# TYPK.net
KiCad netlist of a schematic drawn in Altium Designer
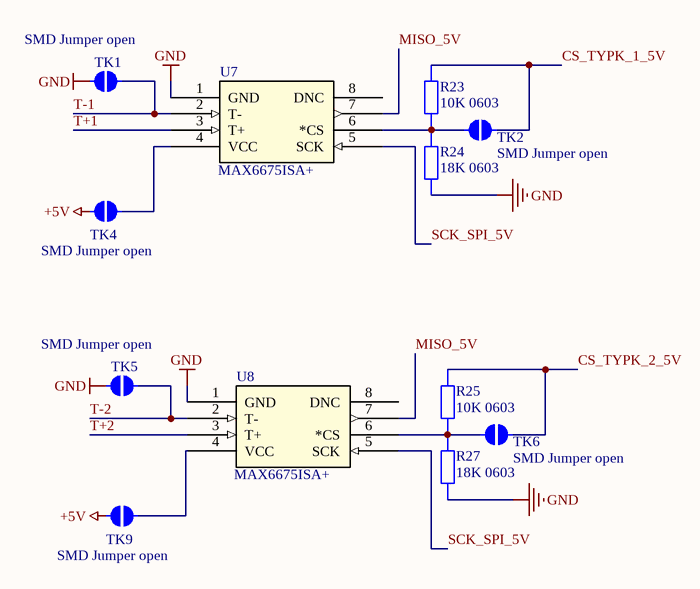
[diagram p0: TYPK.SchDoc]

(export (version "E")
  (design (tool "Eeschema 10.0.6"))
  (components
    (comp (ref "R23")
      (value "10K 0603")
      (footprint "STACKPOLE CSR0603")
      (description "Resistor with multiple footprints")
      (fields (field (name "Comment") "SMD Resistor"))
      (libsource (lib "Standardbauteile") (part "SMD Resistor"))
    )
    (comp (ref "R24")
      (value "18K 0603")
      (footprint "STACKPOLE CSR0603")
      (description "Resistor with multiple footprints")
      (fields (field (name "Comment") "SMD Resistor"))
      (libsource (lib "Standardbauteile") (part "SMD Resistor"))
    )
    (comp (ref "R25")
      (value "10K 0603")
      (footprint "STACKPOLE CSR0603")
      (description "Resistor with multiple footprints")
      (fields (field (name "Comment") "SMD Resistor"))
      (libsource (lib "Standardbauteile") (part "SMD Resistor"))
    )
    (comp (ref "R27")
      (value "18K 0603")
      (footprint "STACKPOLE CSR0603")
      (description "Resistor with multiple footprints")
      (fields (field (name "Comment") "SMD Resistor"))
      (libsource (lib "Standardbauteile") (part "SMD Resistor"))
    )
    (comp (ref "TK1")
      (value "SMD Jumper open")
      (footprint "SMD-JUMPER-OPEN")
      (libsource (lib "Standardbauteile") (part "SMD Jumper open"))
    )
    (comp (ref "TK2")
      (value "SMD Jumper open")
      (footprint "SMD-JUMPER-OPEN")
      (libsource (lib "Standardbauteile") (part "SMD Jumper open"))
    )
    (comp (ref "TK4")
      (value "SMD Jumper open")
      (footprint "SMD-JUMPER-OPEN")
      (libsource (lib "Standardbauteile") (part "SMD Jumper open"))
    )
    (comp (ref "TK5")
      (value "SMD Jumper open")
      (footprint "SMD-JUMPER-OPEN")
      (libsource (lib "Standardbauteile") (part "SMD Jumper open"))
    )
    (comp (ref "TK6")
      (value "SMD Jumper open")
      (footprint "SMD-JUMPER-OPEN")
      (libsource (lib "Standardbauteile") (part "SMD Jumper open"))
    )
    (comp (ref "TK9")
      (value "SMD Jumper open")
      (footprint "SMD-JUMPER-OPEN")
      (libsource (lib "Standardbauteile") (part "SMD Jumper open"))
    )
    (comp (ref "U7")
      (value "MAX6675ISA+")
      (footprint "SOIC8")
      (fields
        (field (name "MANUFACTURER_PART_NUMBER") "MAX31855KASA+")
        (field (name "COPYRIGHT") "Copyright (C) 2018 Accelerated Designs. All rights reserved")
      )
      (libsource (lib "Eric") (part "MAX31855KASA+"))
    )
    (comp (ref "U8")
      (value "MAX6675ISA+")
      (footprint "SOIC8")
      (fields
        (field (name "MANUFACTURER_PART_NUMBER") "MAX31855KASA+")
        (field (name "COPYRIGHT") "Copyright (C) 2018 Accelerated Designs. All rights reserved")
      )
      (libsource (lib "Eric") (part "MAX31855KASA+"))
    )
  )
  (nets
    (net (code "1") (name "+5V") (class "Default")
      (node (ref "TK4") (pin "1") (pinfunction "1_1") (pintype "passive"))
      (node (ref "TK9") (pin "1") (pinfunction "1_1") (pintype "passive"))
    )
    (net (code "2") (name "/CS_TYPK_1_5V") (class "Default")
      (node (ref "R23") (pin "2") (pinfunction "2_2") (pintype "passive"))
      (node (ref "TK2") (pin "2") (pinfunction "2_2") (pintype "passive"))
    )
    (net (code "3") (name "/CS_TYPK_2_5V") (class "Default")
      (node (ref "R25") (pin "2") (pinfunction "2_2") (pintype "passive"))
      (node (ref "TK6") (pin "2") (pinfunction "2_2") (pintype "passive"))
    )
    (net (code "4") (name "/MISO_5V") (class "Default")
      (node (ref "U7") (pin "7") (pinfunction "SO_7") (pintype "output"))
      (node (ref "U8") (pin "7") (pinfunction "SO_7") (pintype "output"))
    )
    (net (code "5") (name "/SCK_SPI_5V") (class "Default")
      (node (ref "U7") (pin "5") (pinfunction "SCK_5") (pintype "input"))
      (node (ref "U8") (pin "5") (pinfunction "SCK_5") (pintype "input"))
    )
    (net (code "6") (name "/T+1") (class "Default")
      (node (ref "U7") (pin "3") (pinfunction "T+_3") (pintype "input"))
    )
    (net (code "7") (name "/T+2") (class "Default")
      (node (ref "U8") (pin "3") (pinfunction "T+_3") (pintype "input"))
    )
    (net (code "8") (name "/T-1") (class "Default")
      (node (ref "TK1") (pin "2") (pinfunction "2_2") (pintype "passive"))
      (node (ref "U7") (pin "2") (pinfunction "T-_2") (pintype "input"))
    )
    (net (code "9") (name "/T-2") (class "Default")
      (node (ref "TK5") (pin "2") (pinfunction "2_2") (pintype "passive"))
      (node (ref "U8") (pin "2") (pinfunction "T-_2") (pintype "input"))
    )
    (net (code "10") (name "GND") (class "Default")
      (node (ref "R24") (pin "1") (pinfunction "1_1") (pintype "passive"))
      (node (ref "R27") (pin "1") (pinfunction "1_1") (pintype "passive"))
      (node (ref "TK1") (pin "1") (pinfunction "1_1") (pintype "passive"))
      (node (ref "TK5") (pin "1") (pinfunction "1_1") (pintype "passive"))
      (node (ref "U7") (pin "1") (pinfunction "GND_1") (pintype "power_in"))
      (node (ref "U8") (pin "1") (pinfunction "GND_1") (pintype "power_in"))
    )
    (net (code "11") (name "Net-(U7-*CS)") (class "Default")
      (node (ref "R23") (pin "1") (pinfunction "1_1") (pintype "passive"))
      (node (ref "R24") (pin "2") (pinfunction "2_2") (pintype "passive"))
      (node (ref "TK2") (pin "1") (pinfunction "1_1") (pintype "passive"))
      (node (ref "U7") (pin "6") (pinfunction "*CS_6") (pintype "passive"))
    )
    (net (code "12") (name "Net-(U7-VCC)") (class "Default")
      (node (ref "TK4") (pin "2") (pinfunction "2_2") (pintype "passive"))
      (node (ref "U7") (pin "4") (pinfunction "VCC_4") (pintype "power_in"))
    )
    (net (code "13") (name "Net-(U8-*CS)") (class "Default")
      (node (ref "R25") (pin "1") (pinfunction "1_1") (pintype "passive"))
      (node (ref "R27") (pin "2") (pinfunction "2_2") (pintype "passive"))
      (node (ref "TK6") (pin "1") (pinfunction "1_1") (pintype "passive"))
      (node (ref "U8") (pin "6") (pinfunction "*CS_6") (pintype "passive"))
    )
    (net (code "14") (name "Net-(U8-VCC)") (class "Default")
      (node (ref "TK9") (pin "2") (pinfunction "2_2") (pintype "passive"))
      (node (ref "U8") (pin "4") (pinfunction "VCC_4") (pintype "power_in"))
    )
    (net (code "15") (name "unconnected-(U7-DNC-Pad8)") (class "Default")
      (node (ref "U7") (pin "8") (pinfunction "DNC_8") (pintype "passive"))
    )
    (net (code "16") (name "unconnected-(U8-DNC-Pad8)") (class "Default")
      (node (ref "U8") (pin "8") (pinfunction "DNC_8") (pintype "passive"))
    )
  )
)
